# Vers_4_Moppy_Board.net
KiCad netlist of a schematic drawn in EAGLE
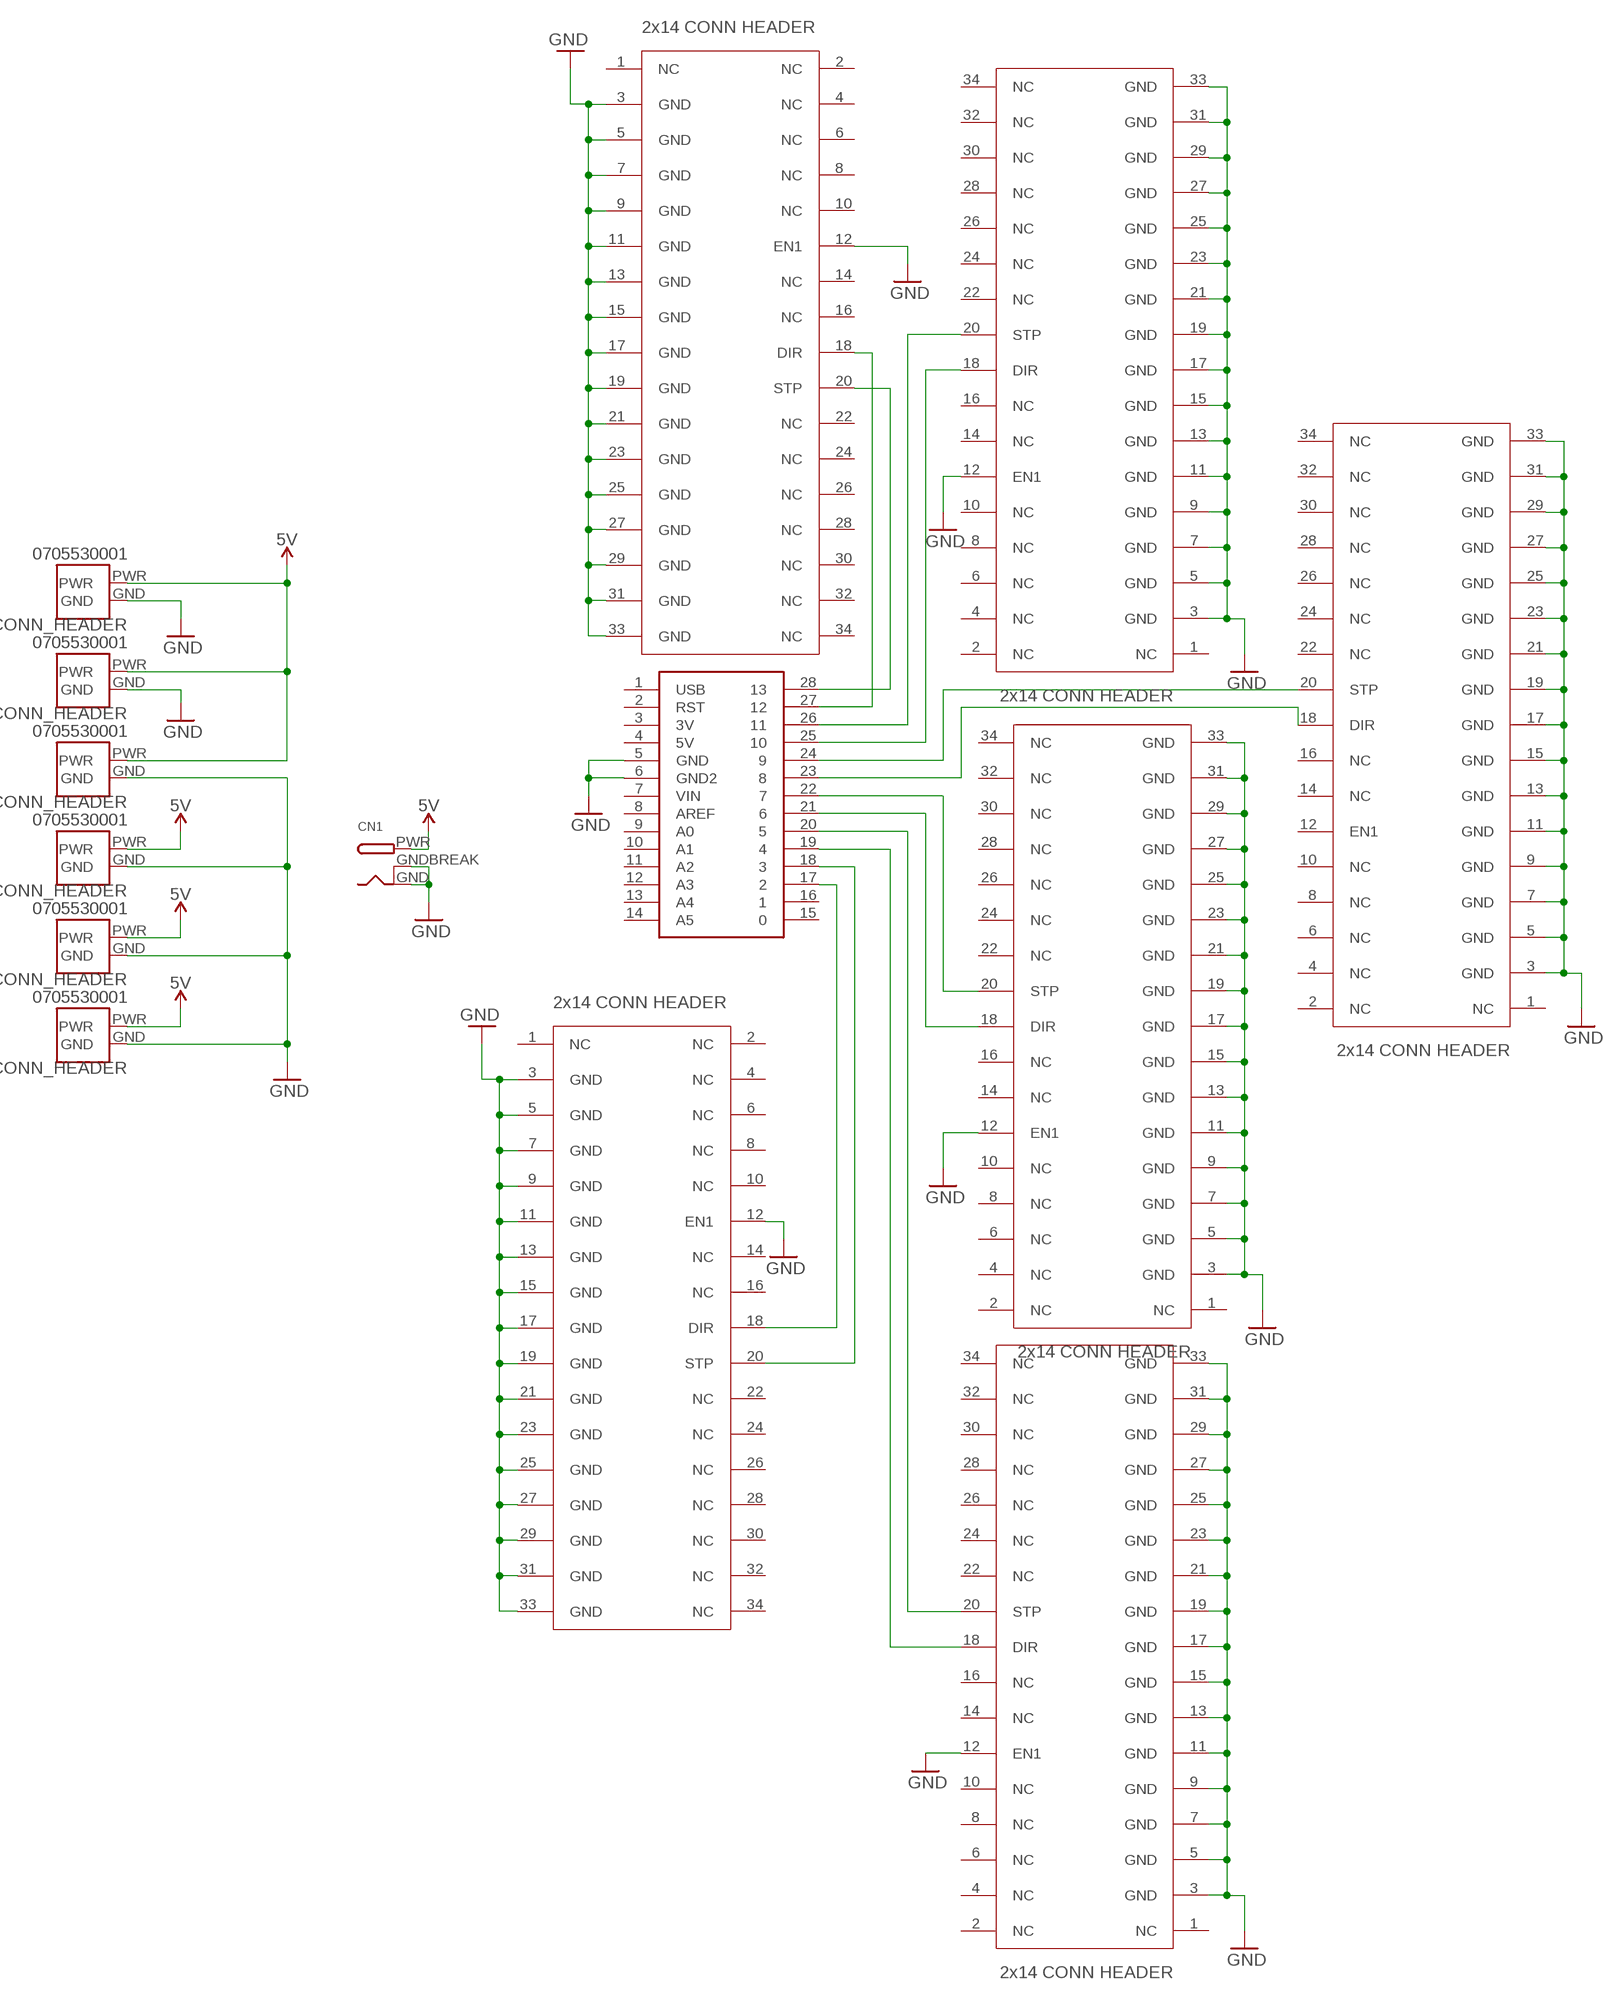
[diagram p0: schematic, sheet 1]

(export (version "E")
  (design (tool "Eeschema 10.0.6"))
  (components
    (comp (ref "CN1")
      (value "DCBARRELPTH")
      (footprint "eagle-import:DCJACK_2MM_PTH")
      (libsource (lib "eagle-import") (part "DCBARRELPTH"))
    )
    (comp (ref "U$1")
      (value "2X14_CONN_HEADER")
      (footprint "eagle-import:2X17_CONN_HEADER")
      (libsource (lib "eagle-import") (part "2X14_CONN_HEADER"))
    )
    (comp (ref "U$2")
      (value "2X14_CONN_HEADER")
      (footprint "eagle-import:2X17_CONN_HEADER")
      (libsource (lib "eagle-import") (part "2X14_CONN_HEADER"))
    )
    (comp (ref "U$3")
      (value "2X14_CONN_HEADER")
      (footprint "eagle-import:2X17_CONN_HEADER")
      (libsource (lib "eagle-import") (part "2X14_CONN_HEADER"))
    )
    (comp (ref "U$4")
      (value "2X14_CONN_HEADER")
      (footprint "eagle-import:2X17_CONN_HEADER")
      (libsource (lib "eagle-import") (part "2X14_CONN_HEADER"))
    )
    (comp (ref "U$5")
      (value "2X14_CONN_HEADER")
      (footprint "eagle-import:2X17_CONN_HEADER")
      (libsource (lib "eagle-import") (part "2X14_CONN_HEADER"))
    )
    (comp (ref "U$6")
      (value "2X14_CONN_HEADER")
      (footprint "eagle-import:2X17_CONN_HEADER")
      (libsource (lib "eagle-import") (part "2X14_CONN_HEADER"))
    )
    (comp (ref "U$8")
      (value "METROMINI")
      (footprint "eagle-import:METROMINI")
      (libsource (lib "eagle-import") (part "METROMINI"))
    )
    (comp (ref "X1")
      (value "0705530001")
      (footprint "eagle-import:MOLEX_0705530001")
      (fields (field (name "DIGI-KEY_PART_NUMBER") "WM4900-ND") (field (name "MF") "Molex"))
      (libsource (lib "eagle-import") (part "0705530001"))
    )
    (comp (ref "X2")
      (value "0705530001")
      (footprint "eagle-import:MOLEX_0705530001")
      (fields (field (name "DIGI-KEY_PART_NUMBER") "WM4900-ND") (field (name "MF") "Molex"))
      (libsource (lib "eagle-import") (part "0705530001"))
    )
    (comp (ref "X3")
      (value "0705530001")
      (footprint "eagle-import:MOLEX_0705530001")
      (fields (field (name "DIGI-KEY_PART_NUMBER") "WM4900-ND") (field (name "MF") "Molex"))
      (libsource (lib "eagle-import") (part "0705530001"))
    )
    (comp (ref "X4")
      (value "0705530001")
      (footprint "eagle-import:MOLEX_0705530001")
      (fields (field (name "DIGI-KEY_PART_NUMBER") "WM4900-ND") (field (name "MF") "Molex"))
      (libsource (lib "eagle-import") (part "0705530001"))
    )
    (comp (ref "X5")
      (value "0705530001")
      (footprint "eagle-import:MOLEX_0705530001")
      (fields (field (name "DIGI-KEY_PART_NUMBER") "WM4900-ND") (field (name "MF") "Molex"))
      (libsource (lib "eagle-import") (part "0705530001"))
    )
    (comp (ref "X6")
      (value "0705530001")
      (footprint "eagle-import:MOLEX_0705530001")
      (fields (field (name "DIGI-KEY_PART_NUMBER") "WM4900-ND") (field (name "MF") "Molex"))
      (libsource (lib "eagle-import") (part "0705530001"))
    )
  )
  (nets
    (net (code "1") (name "5V") (class "Default")
      (node (ref "CN1") (pin "PWR") (pinfunction "PWR_PWR") (pintype "power_in"))
      (node (ref "X1") (pin "PWR") (pinfunction "PWR_PWR") (pintype "passive"))
      (node (ref "X2") (pin "PWR") (pinfunction "PWR_PWR") (pintype "passive"))
      (node (ref "X3") (pin "PWR") (pinfunction "PWR_PWR") (pintype "passive"))
      (node (ref "X4") (pin "PWR") (pinfunction "PWR_PWR") (pintype "passive"))
      (node (ref "X5") (pin "PWR") (pinfunction "PWR_PWR") (pintype "passive"))
      (node (ref "X6") (pin "PWR") (pinfunction "PWR_PWR") (pintype "passive"))
    )
    (net (code "2") (name "GND") (class "Default")
      (node (ref "CN1") (pin "GND") (pinfunction "GND_GND") (pintype "power_in"))
      (node (ref "CN1") (pin "GNDBREAK") (pinfunction "GNDBREAK_GNDBREAK") (pintype "power_in"))
      (node (ref "U$1") (pin "11") (pinfunction "GND_11") (pintype "bidirectional"))
      (node (ref "U$1") (pin "12") (pinfunction "EN1_12") (pintype "bidirectional"))
      (node (ref "U$1") (pin "13") (pinfunction "GND_13") (pintype "bidirectional"))
      (node (ref "U$1") (pin "15") (pinfunction "GND_15") (pintype "bidirectional"))
      (node (ref "U$1") (pin "17") (pinfunction "GND_17") (pintype "bidirectional"))
      (node (ref "U$1") (pin "19") (pinfunction "GND_19") (pintype "bidirectional"))
      (node (ref "U$1") (pin "21") (pinfunction "GND_21") (pintype "bidirectional"))
      (node (ref "U$1") (pin "23") (pinfunction "GND_23") (pintype "bidirectional"))
      (node (ref "U$1") (pin "25") (pinfunction "GND_25") (pintype "bidirectional"))
      (node (ref "U$1") (pin "27") (pinfunction "GND_27") (pintype "bidirectional"))
      (node (ref "U$1") (pin "29") (pinfunction "GND_29") (pintype "bidirectional"))
      (node (ref "U$1") (pin "3") (pinfunction "GND_3") (pintype "bidirectional"))
      (node (ref "U$1") (pin "31") (pinfunction "GND_31") (pintype "bidirectional"))
      (node (ref "U$1") (pin "33") (pinfunction "GND_33") (pintype "bidirectional"))
      (node (ref "U$1") (pin "5") (pinfunction "GND_5") (pintype "bidirectional"))
      (node (ref "U$1") (pin "7") (pinfunction "GND_7") (pintype "bidirectional"))
      (node (ref "U$1") (pin "9") (pinfunction "GND_9") (pintype "bidirectional"))
      (node (ref "U$2") (pin "11") (pinfunction "GND_11") (pintype "bidirectional"))
      (node (ref "U$2") (pin "12") (pinfunction "EN1_12") (pintype "bidirectional"))
      (node (ref "U$2") (pin "13") (pinfunction "GND_13") (pintype "bidirectional"))
      (node (ref "U$2") (pin "15") (pinfunction "GND_15") (pintype "bidirectional"))
      (node (ref "U$2") (pin "17") (pinfunction "GND_17") (pintype "bidirectional"))
      (node (ref "U$2") (pin "19") (pinfunction "GND_19") (pintype "bidirectional"))
      (node (ref "U$2") (pin "21") (pinfunction "GND_21") (pintype "bidirectional"))
      (node (ref "U$2") (pin "23") (pinfunction "GND_23") (pintype "bidirectional"))
      (node (ref "U$2") (pin "25") (pinfunction "GND_25") (pintype "bidirectional"))
      (node (ref "U$2") (pin "27") (pinfunction "GND_27") (pintype "bidirectional"))
      (node (ref "U$2") (pin "29") (pinfunction "GND_29") (pintype "bidirectional"))
      (node (ref "U$2") (pin "3") (pinfunction "GND_3") (pintype "bidirectional"))
      (node (ref "U$2") (pin "31") (pinfunction "GND_31") (pintype "bidirectional"))
      (node (ref "U$2") (pin "33") (pinfunction "GND_33") (pintype "bidirectional"))
      (node (ref "U$2") (pin "5") (pinfunction "GND_5") (pintype "bidirectional"))
      (node (ref "U$2") (pin "7") (pinfunction "GND_7") (pintype "bidirectional"))
      (node (ref "U$2") (pin "9") (pinfunction "GND_9") (pintype "bidirectional"))
      (node (ref "U$3") (pin "11") (pinfunction "GND_11") (pintype "bidirectional"))
      (node (ref "U$3") (pin "12") (pinfunction "EN1_12") (pintype "bidirectional"))
      (node (ref "U$3") (pin "13") (pinfunction "GND_13") (pintype "bidirectional"))
      (node (ref "U$3") (pin "15") (pinfunction "GND_15") (pintype "bidirectional"))
      (node (ref "U$3") (pin "17") (pinfunction "GND_17") (pintype "bidirectional"))
      (node (ref "U$3") (pin "19") (pinfunction "GND_19") (pintype "bidirectional"))
      (node (ref "U$3") (pin "21") (pinfunction "GND_21") (pintype "bidirectional"))
      (node (ref "U$3") (pin "23") (pinfunction "GND_23") (pintype "bidirectional"))
      (node (ref "U$3") (pin "25") (pinfunction "GND_25") (pintype "bidirectional"))
      (node (ref "U$3") (pin "27") (pinfunction "GND_27") (pintype "bidirectional"))
      (node (ref "U$3") (pin "29") (pinfunction "GND_29") (pintype "bidirectional"))
      (node (ref "U$3") (pin "3") (pinfunction "GND_3") (pintype "bidirectional"))
      (node (ref "U$3") (pin "31") (pinfunction "GND_31") (pintype "bidirectional"))
      (node (ref "U$3") (pin "33") (pinfunction "GND_33") (pintype "bidirectional"))
      (node (ref "U$3") (pin "5") (pinfunction "GND_5") (pintype "bidirectional"))
      (node (ref "U$3") (pin "7") (pinfunction "GND_7") (pintype "bidirectional"))
      (node (ref "U$3") (pin "9") (pinfunction "GND_9") (pintype "bidirectional"))
      (node (ref "U$4") (pin "11") (pinfunction "GND_11") (pintype "bidirectional"))
      (node (ref "U$4") (pin "12") (pinfunction "EN1_12") (pintype "bidirectional"))
      (node (ref "U$4") (pin "13") (pinfunction "GND_13") (pintype "bidirectional"))
      (node (ref "U$4") (pin "15") (pinfunction "GND_15") (pintype "bidirectional"))
      (node (ref "U$4") (pin "17") (pinfunction "GND_17") (pintype "bidirectional"))
      (node (ref "U$4") (pin "19") (pinfunction "GND_19") (pintype "bidirectional"))
      (node (ref "U$4") (pin "21") (pinfunction "GND_21") (pintype "bidirectional"))
      (node (ref "U$4") (pin "23") (pinfunction "GND_23") (pintype "bidirectional"))
      (node (ref "U$4") (pin "25") (pinfunction "GND_25") (pintype "bidirectional"))
      (node (ref "U$4") (pin "27") (pinfunction "GND_27") (pintype "bidirectional"))
      (node (ref "U$4") (pin "29") (pinfunction "GND_29") (pintype "bidirectional"))
      (node (ref "U$4") (pin "3") (pinfunction "GND_3") (pintype "bidirectional"))
      (node (ref "U$4") (pin "31") (pinfunction "GND_31") (pintype "bidirectional"))
      (node (ref "U$4") (pin "33") (pinfunction "GND_33") (pintype "bidirectional"))
      (node (ref "U$4") (pin "5") (pinfunction "GND_5") (pintype "bidirectional"))
      (node (ref "U$4") (pin "7") (pinfunction "GND_7") (pintype "bidirectional"))
      (node (ref "U$4") (pin "9") (pinfunction "GND_9") (pintype "bidirectional"))
      (node (ref "U$5") (pin "11") (pinfunction "GND_11") (pintype "bidirectional"))
      (node (ref "U$5") (pin "12") (pinfunction "EN1_12") (pintype "bidirectional"))
      (node (ref "U$5") (pin "13") (pinfunction "GND_13") (pintype "bidirectional"))
      (node (ref "U$5") (pin "15") (pinfunction "GND_15") (pintype "bidirectional"))
      (node (ref "U$5") (pin "17") (pinfunction "GND_17") (pintype "bidirectional"))
      (node (ref "U$5") (pin "19") (pinfunction "GND_19") (pintype "bidirectional"))
      (node (ref "U$5") (pin "21") (pinfunction "GND_21") (pintype "bidirectional"))
      (node (ref "U$5") (pin "23") (pinfunction "GND_23") (pintype "bidirectional"))
      (node (ref "U$5") (pin "25") (pinfunction "GND_25") (pintype "bidirectional"))
      (node (ref "U$5") (pin "27") (pinfunction "GND_27") (pintype "bidirectional"))
      (node (ref "U$5") (pin "29") (pinfunction "GND_29") (pintype "bidirectional"))
      (node (ref "U$5") (pin "3") (pinfunction "GND_3") (pintype "bidirectional"))
      (node (ref "U$5") (pin "31") (pinfunction "GND_31") (pintype "bidirectional"))
      (node (ref "U$5") (pin "33") (pinfunction "GND_33") (pintype "bidirectional"))
      (node (ref "U$5") (pin "5") (pinfunction "GND_5") (pintype "bidirectional"))
      (node (ref "U$5") (pin "7") (pinfunction "GND_7") (pintype "bidirectional"))
      (node (ref "U$5") (pin "9") (pinfunction "GND_9") (pintype "bidirectional"))
      (node (ref "U$6") (pin "11") (pinfunction "GND_11") (pintype "bidirectional"))
      (node (ref "U$6") (pin "13") (pinfunction "GND_13") (pintype "bidirectional"))
      (node (ref "U$6") (pin "15") (pinfunction "GND_15") (pintype "bidirectional"))
      (node (ref "U$6") (pin "17") (pinfunction "GND_17") (pintype "bidirectional"))
      (node (ref "U$6") (pin "19") (pinfunction "GND_19") (pintype "bidirectional"))
      (node (ref "U$6") (pin "21") (pinfunction "GND_21") (pintype "bidirectional"))
      (node (ref "U$6") (pin "23") (pinfunction "GND_23") (pintype "bidirectional"))
      (node (ref "U$6") (pin "25") (pinfunction "GND_25") (pintype "bidirectional"))
      (node (ref "U$6") (pin "27") (pinfunction "GND_27") (pintype "bidirectional"))
      (node (ref "U$6") (pin "29") (pinfunction "GND_29") (pintype "bidirectional"))
      (node (ref "U$6") (pin "3") (pinfunction "GND_3") (pintype "bidirectional"))
      (node (ref "U$6") (pin "31") (pinfunction "GND_31") (pintype "bidirectional"))
      (node (ref "U$6") (pin "33") (pinfunction "GND_33") (pintype "bidirectional"))
      (node (ref "U$6") (pin "5") (pinfunction "GND_5") (pintype "bidirectional"))
      (node (ref "U$6") (pin "7") (pinfunction "GND_7") (pintype "bidirectional"))
      (node (ref "U$6") (pin "9") (pinfunction "GND_9") (pintype "bidirectional"))
      (node (ref "U$8") (pin "5") (pinfunction "GND_5") (pintype "bidirectional"))
      (node (ref "U$8") (pin "6") (pinfunction "GND2_6") (pintype "bidirectional"))
      (node (ref "X1") (pin "GND") (pinfunction "GND_GND") (pintype "passive"))
      (node (ref "X2") (pin "GND") (pinfunction "GND_GND") (pintype "passive"))
      (node (ref "X3") (pin "GND") (pinfunction "GND_GND") (pintype "passive"))
      (node (ref "X4") (pin "GND") (pinfunction "GND_GND") (pintype "passive"))
      (node (ref "X5") (pin "GND") (pinfunction "GND_GND") (pintype "passive"))
      (node (ref "X6") (pin "GND") (pinfunction "GND_GND") (pintype "passive"))
    )
    (net (code "3") (name "Net-(U$1-DIR)") (class "Default")
      (node (ref "U$1") (pin "18") (pinfunction "DIR_18") (pintype "bidirectional"))
      (node (ref "U$8") (pin "17") (pinfunction "2_17") (pintype "bidirectional"))
    )
    (net (code "4") (name "Net-(U$1-STP)") (class "Default")
      (node (ref "U$1") (pin "20") (pinfunction "STP_20") (pintype "bidirectional"))
      (node (ref "U$8") (pin "18") (pinfunction "3_18") (pintype "bidirectional"))
    )
    (net (code "5") (name "Net-(U$2-DIR)") (class "Default")
      (node (ref "U$2") (pin "18") (pinfunction "DIR_18") (pintype "bidirectional"))
      (node (ref "U$8") (pin "27") (pinfunction "12_27") (pintype "bidirectional"))
    )
    (net (code "6") (name "Net-(U$2-STP)") (class "Default")
      (node (ref "U$2") (pin "20") (pinfunction "STP_20") (pintype "bidirectional"))
      (node (ref "U$8") (pin "28") (pinfunction "13_28") (pintype "bidirectional"))
    )
    (net (code "7") (name "Net-(U$3-DIR)") (class "Default")
      (node (ref "U$3") (pin "18") (pinfunction "DIR_18") (pintype "bidirectional"))
      (node (ref "U$8") (pin "25") (pinfunction "10_25") (pintype "bidirectional"))
    )
    (net (code "8") (name "Net-(U$3-STP)") (class "Default")
      (node (ref "U$3") (pin "20") (pinfunction "STP_20") (pintype "bidirectional"))
      (node (ref "U$8") (pin "26") (pinfunction "11_26") (pintype "bidirectional"))
    )
    (net (code "9") (name "Net-(U$4-DIR)") (class "Default")
      (node (ref "U$4") (pin "18") (pinfunction "DIR_18") (pintype "bidirectional"))
      (node (ref "U$8") (pin "19") (pinfunction "4_19") (pintype "bidirectional"))
    )
    (net (code "10") (name "Net-(U$4-STP)") (class "Default")
      (node (ref "U$4") (pin "20") (pinfunction "STP_20") (pintype "bidirectional"))
      (node (ref "U$8") (pin "20") (pinfunction "5_20") (pintype "bidirectional"))
    )
    (net (code "11") (name "Net-(U$5-DIR)") (class "Default")
      (node (ref "U$5") (pin "18") (pinfunction "DIR_18") (pintype "bidirectional"))
      (node (ref "U$8") (pin "21") (pinfunction "6_21") (pintype "bidirectional"))
    )
    (net (code "12") (name "Net-(U$5-STP)") (class "Default")
      (node (ref "U$5") (pin "20") (pinfunction "STP_20") (pintype "bidirectional"))
      (node (ref "U$8") (pin "22") (pinfunction "7_22") (pintype "bidirectional"))
    )
    (net (code "13") (name "Net-(U$6-DIR)") (class "Default")
      (node (ref "U$6") (pin "18") (pinfunction "DIR_18") (pintype "bidirectional"))
      (node (ref "U$8") (pin "23") (pinfunction "8_23") (pintype "bidirectional"))
    )
    (net (code "14") (name "Net-(U$6-STP)") (class "Default")
      (node (ref "U$6") (pin "20") (pinfunction "STP_20") (pintype "bidirectional"))
      (node (ref "U$8") (pin "24") (pinfunction "9_24") (pintype "bidirectional"))
    )
    (net (code "15") (name "unconnected-(U$1-NC-Pad1)") (class "Default")
      (node (ref "U$1") (pin "1") (pinfunction "NC_1") (pintype "bidirectional"))
    )
    (net (code "16") (name "unconnected-(U$1-NC-Pad2)") (class "Default")
      (node (ref "U$1") (pin "2") (pinfunction "NC_2") (pintype "bidirectional"))
    )
    (net (code "17") (name "unconnected-(U$1-NC-Pad4)") (class "Default")
      (node (ref "U$1") (pin "4") (pinfunction "NC_4") (pintype "bidirectional"))
    )
    (net (code "18") (name "unconnected-(U$1-NC-Pad6)") (class "Default")
      (node (ref "U$1") (pin "6") (pinfunction "NC_6") (pintype "bidirectional"))
    )
    (net (code "19") (name "unconnected-(U$1-NC-Pad8)") (class "Default")
      (node (ref "U$1") (pin "8") (pinfunction "NC_8") (pintype "bidirectional"))
    )
    (net (code "20") (name "unconnected-(U$1-NC-Pad10)") (class "Default")
      (node (ref "U$1") (pin "10") (pinfunction "NC_10") (pintype "bidirectional"))
    )
    (net (code "21") (name "unconnected-(U$1-NC-Pad14)") (class "Default")
      (node (ref "U$1") (pin "14") (pinfunction "NC_14") (pintype "bidirectional"))
    )
    (net (code "22") (name "unconnected-(U$1-NC-Pad16)") (class "Default")
      (node (ref "U$1") (pin "16") (pinfunction "NC_16") (pintype "bidirectional"))
    )
    (net (code "23") (name "unconnected-(U$1-NC-Pad22)") (class "Default")
      (node (ref "U$1") (pin "22") (pinfunction "NC_22") (pintype "bidirectional"))
    )
    (net (code "24") (name "unconnected-(U$1-NC-Pad24)") (class "Default")
      (node (ref "U$1") (pin "24") (pinfunction "NC_24") (pintype "bidirectional"))
    )
    (net (code "25") (name "unconnected-(U$1-NC-Pad26)") (class "Default")
      (node (ref "U$1") (pin "26") (pinfunction "NC_26") (pintype "bidirectional"))
    )
    (net (code "26") (name "unconnected-(U$1-NC-Pad28)") (class "Default")
      (node (ref "U$1") (pin "28") (pinfunction "NC_28") (pintype "bidirectional"))
    )
    (net (code "27") (name "unconnected-(U$1-NC-Pad30)") (class "Default")
      (node (ref "U$1") (pin "30") (pinfunction "NC_30") (pintype "bidirectional"))
    )
    (net (code "28") (name "unconnected-(U$1-NC-Pad32)") (class "Default")
      (node (ref "U$1") (pin "32") (pinfunction "NC_32") (pintype "bidirectional"))
    )
    (net (code "29") (name "unconnected-(U$1-NC-Pad34)") (class "Default")
      (node (ref "U$1") (pin "34") (pinfunction "NC_34") (pintype "bidirectional"))
    )
    (net (code "30") (name "unconnected-(U$2-NC-Pad1)") (class "Default")
      (node (ref "U$2") (pin "1") (pinfunction "NC_1") (pintype "bidirectional"))
    )
    (net (code "31") (name "unconnected-(U$2-NC-Pad2)") (class "Default")
      (node (ref "U$2") (pin "2") (pinfunction "NC_2") (pintype "bidirectional"))
    )
    (net (code "32") (name "unconnected-(U$2-NC-Pad4)") (class "Default")
      (node (ref "U$2") (pin "4") (pinfunction "NC_4") (pintype "bidirectional"))
    )
    (net (code "33") (name "unconnected-(U$2-NC-Pad6)") (class "Default")
      (node (ref "U$2") (pin "6") (pinfunction "NC_6") (pintype "bidirectional"))
    )
    (net (code "34") (name "unconnected-(U$2-NC-Pad8)") (class "Default")
      (node (ref "U$2") (pin "8") (pinfunction "NC_8") (pintype "bidirectional"))
    )
    (net (code "35") (name "unconnected-(U$2-NC-Pad10)") (class "Default")
      (node (ref "U$2") (pin "10") (pinfunction "NC_10") (pintype "bidirectional"))
    )
    (net (code "36") (name "unconnected-(U$2-NC-Pad14)") (class "Default")
      (node (ref "U$2") (pin "14") (pinfunction "NC_14") (pintype "bidirectional"))
    )
    (net (code "37") (name "unconnected-(U$2-NC-Pad16)") (class "Default")
      (node (ref "U$2") (pin "16") (pinfunction "NC_16") (pintype "bidirectional"))
    )
    (net (code "38") (name "unconnected-(U$2-NC-Pad22)") (class "Default")
      (node (ref "U$2") (pin "22") (pinfunction "NC_22") (pintype "bidirectional"))
    )
    (net (code "39") (name "unconnected-(U$2-NC-Pad24)") (class "Default")
      (node (ref "U$2") (pin "24") (pinfunction "NC_24") (pintype "bidirectional"))
    )
    (net (code "40") (name "unconnected-(U$2-NC-Pad26)") (class "Default")
      (node (ref "U$2") (pin "26") (pinfunction "NC_26") (pintype "bidirectional"))
    )
    (net (code "41") (name "unconnected-(U$2-NC-Pad28)") (class "Default")
      (node (ref "U$2") (pin "28") (pinfunction "NC_28") (pintype "bidirectional"))
    )
    (net (code "42") (name "unconnected-(U$2-NC-Pad30)") (class "Default")
      (node (ref "U$2") (pin "30") (pinfunction "NC_30") (pintype "bidirectional"))
    )
    (net (code "43") (name "unconnected-(U$2-NC-Pad32)") (class "Default")
      (node (ref "U$2") (pin "32") (pinfunction "NC_32") (pintype "bidirectional"))
    )
    (net (code "44") (name "unconnected-(U$2-NC-Pad34)") (class "Default")
      (node (ref "U$2") (pin "34") (pinfunction "NC_34") (pintype "bidirectional"))
    )
    (net (code "45") (name "unconnected-(U$3-NC-Pad1)") (class "Default")
      (node (ref "U$3") (pin "1") (pinfunction "NC_1") (pintype "bidirectional"))
    )
    (net (code "46") (name "unconnected-(U$3-NC-Pad2)") (class "Default")
      (node (ref "U$3") (pin "2") (pinfunction "NC_2") (pintype "bidirectional"))
    )
    (net (code "47") (name "unconnected-(U$3-NC-Pad4)") (class "Default")
      (node (ref "U$3") (pin "4") (pinfunction "NC_4") (pintype "bidirectional"))
    )
    (net (code "48") (name "unconnected-(U$3-NC-Pad6)") (class "Default")
      (node (ref "U$3") (pin "6") (pinfunction "NC_6") (pintype "bidirectional"))
    )
    (net (code "49") (name "unconnected-(U$3-NC-Pad8)") (class "Default")
      (node (ref "U$3") (pin "8") (pinfunction "NC_8") (pintype "bidirectional"))
    )
    (net (code "50") (name "unconnected-(U$3-NC-Pad10)") (class "Default")
      (node (ref "U$3") (pin "10") (pinfunction "NC_10") (pintype "bidirectional"))
    )
    (net (code "51") (name "unconnected-(U$3-NC-Pad14)") (class "Default")
      (node (ref "U$3") (pin "14") (pinfunction "NC_14") (pintype "bidirectional"))
    )
    (net (code "52") (name "unconnected-(U$3-NC-Pad16)") (class "Default")
      (node (ref "U$3") (pin "16") (pinfunction "NC_16") (pintype "bidirectional"))
    )
    (net (code "53") (name "unconnected-(U$3-NC-Pad22)") (class "Default")
      (node (ref "U$3") (pin "22") (pinfunction "NC_22") (pintype "bidirectional"))
    )
    (net (code "54") (name "unconnected-(U$3-NC-Pad24)") (class "Default")
      (node (ref "U$3") (pin "24") (pinfunction "NC_24") (pintype "bidirectional"))
    )
    (net (code "55") (name "unconnected-(U$3-NC-Pad26)") (class "Default")
      (node (ref "U$3") (pin "26") (pinfunction "NC_26") (pintype "bidirectional"))
    )
    (net (code "56") (name "unconnected-(U$3-NC-Pad28)") (class "Default")
      (node (ref "U$3") (pin "28") (pinfunction "NC_28") (pintype "bidirectional"))
    )
    (net (code "57") (name "unconnected-(U$3-NC-Pad30)") (class "Default")
      (node (ref "U$3") (pin "30") (pinfunction "NC_30") (pintype "bidirectional"))
    )
    (net (code "58") (name "unconnected-(U$3-NC-Pad32)") (class "Default")
      (node (ref "U$3") (pin "32") (pinfunction "NC_32") (pintype "bidirectional"))
    )
    (net (code "59") (name "unconnected-(U$3-NC-Pad34)") (class "Default")
      (node (ref "U$3") (pin "34") (pinfunction "NC_34") (pintype "bidirectional"))
    )
    (net (code "60") (name "unconnected-(U$4-NC-Pad1)") (class "Default")
      (node (ref "U$4") (pin "1") (pinfunction "NC_1") (pintype "bidirectional"))
    )
    (net (code "61") (name "unconnected-(U$4-NC-Pad2)") (class "Default")
      (node (ref "U$4") (pin "2") (pinfunction "NC_2") (pintype "bidirectional"))
    )
    (net (code "62") (name "unconnected-(U$4-NC-Pad4)") (class "Default")
      (node (ref "U$4") (pin "4") (pinfunction "NC_4") (pintype "bidirectional"))
    )
    (net (code "63") (name "unconnected-(U$4-NC-Pad6)") (class "Default")
      (node (ref "U$4") (pin "6") (pinfunction "NC_6") (pintype "bidirectional"))
    )
    (net (code "64") (name "unconnected-(U$4-NC-Pad8)") (class "Default")
      (node (ref "U$4") (pin "8") (pinfunction "NC_8") (pintype "bidirectional"))
    )
    (net (code "65") (name "unconnected-(U$4-NC-Pad10)") (class "Default")
      (node (ref "U$4") (pin "10") (pinfunction "NC_10") (pintype "bidirectional"))
    )
    (net (code "66") (name "unconnected-(U$4-NC-Pad14)") (class "Default")
      (node (ref "U$4") (pin "14") (pinfunction "NC_14") (pintype "bidirectional"))
    )
    (net (code "67") (name "unconnected-(U$4-NC-Pad16)") (class "Default")
      (node (ref "U$4") (pin "16") (pinfunction "NC_16") (pintype "bidirectional"))
    )
    (net (code "68") (name "unconnected-(U$4-NC-Pad22)") (class "Default")
      (node (ref "U$4") (pin "22") (pinfunction "NC_22") (pintype "bidirectional"))
    )
    (net (code "69") (name "unconnected-(U$4-NC-Pad24)") (class "Default")
      (node (ref "U$4") (pin "24") (pinfunction "NC_24") (pintype "bidirectional"))
    )
    (net (code "70") (name "unconnected-(U$4-NC-Pad26)") (class "Default")
      (node (ref "U$4") (pin "26") (pinfunction "NC_26") (pintype "bidirectional"))
    )
    (net (code "71") (name "unconnected-(U$4-NC-Pad28)") (class "Default")
      (node (ref "U$4") (pin "28") (pinfunction "NC_28") (pintype "bidirectional"))
    )
    (net (code "72") (name "unconnected-(U$4-NC-Pad30)") (class "Default")
      (node (ref "U$4") (pin "30") (pinfunction "NC_30") (pintype "bidirectional"))
    )
    (net (code "73") (name "unconnected-(U$4-NC-Pad32)") (class "Default")
      (node (ref "U$4") (pin "32") (pinfunction "NC_32") (pintype "bidirectional"))
    )
    (net (code "74") (name "unconnected-(U$4-NC-Pad34)") (class "Default")
      (node (ref "U$4") (pin "34") (pinfunction "NC_34") (pintype "bidirectional"))
    )
    (net (code "75") (name "unconnected-(U$5-NC-Pad1)") (class "Default")
      (node (ref "U$5") (pin "1") (pinfunction "NC_1") (pintype "bidirectional"))
    )
    (net (code "76") (name "unconnected-(U$5-NC-Pad2)") (class "Default")
      (node (ref "U$5") (pin "2") (pinfunction "NC_2") (pintype "bidirectional"))
    )
    (net (code "77") (name "unconnected-(U$5-NC-Pad4)") (class "Default")
      (node (ref "U$5") (pin "4") (pinfunction "NC_4") (pintype "bidirectional"))
    )
    (net (code "78") (name "unconnected-(U$5-NC-Pad6)") (class "Default")
      (node (ref "U$5") (pin "6") (pinfunction "NC_6") (pintype "bidirectional"))
    )
    (net (code "79") (name "unconnected-(U$5-NC-Pad8)") (class "Default")
      (node (ref "U$5") (pin "8") (pinfunction "NC_8") (pintype "bidirectional"))
    )
    (net (code "80") (name "unconnected-(U$5-NC-Pad10)") (class "Default")
      (node (ref "U$5") (pin "10") (pinfunction "NC_10") (pintype "bidirectional"))
    )
    (net (code "81") (name "unconnected-(U$5-NC-Pad14)") (class "Default")
      (node (ref "U$5") (pin "14") (pinfunction "NC_14") (pintype "bidirectional"))
    )
    (net (code "82") (name "unconnected-(U$5-NC-Pad16)") (class "Default")
      (node (ref "U$5") (pin "16") (pinfunction "NC_16") (pintype "bidirectional"))
    )
    (net (code "83") (name "unconnected-(U$5-NC-Pad22)") (class "Default")
      (node (ref "U$5") (pin "22") (pinfunction "NC_22") (pintype "bidirectional"))
    )
    (net (code "84") (name "unconnected-(U$5-NC-Pad24)") (class "Default")
      (node (ref "U$5") (pin "24") (pinfunction "NC_24") (pintype "bidirectional"))
    )
    (net (code "85") (name "unconnected-(U$5-NC-Pad26)") (class "Default")
      (node (ref "U$5") (pin "26") (pinfunction "NC_26") (pintype "bidirectional"))
    )
    (net (code "86") (name "unconnected-(U$5-NC-Pad28)") (class "Default")
      (node (ref "U$5") (pin "28") (pinfunction "NC_28") (pintype "bidirectional"))
    )
    (net (code "87") (name "unconnected-(U$5-NC-Pad30)") (class "Default")
      (node (ref "U$5") (pin "30") (pinfunction "NC_30") (pintype "bidirectional"))
    )
    (net (code "88") (name "unconnected-(U$5-NC-Pad32)") (class "Default")
      (node (ref "U$5") (pin "32") (pinfunction "NC_32") (pintype "bidirectional"))
    )
    (net (code "89") (name "unconnected-(U$5-NC-Pad34)") (class "Default")
      (node (ref "U$5") (pin "34") (pinfunction "NC_34") (pintype "bidirectional"))
    )
    (net (code "90") (name "unconnected-(U$6-EN1-Pad12)") (class "Default")
      (node (ref "U$6") (pin "12") (pinfunction "EN1_12") (pintype "bidirectional"))
    )
    (net (code "91") (name "unconnected-(U$6-NC-Pad1)") (class "Default")
      (node (ref "U$6") (pin "1") (pinfunction "NC_1") (pintype "bidirectional"))
    )
    (net (code "92") (name "unconnected-(U$6-NC-Pad2)") (class "Default")
      (node (ref "U$6") (pin "2") (pinfunction "NC_2") (pintype "bidirectional"))
    )
    (net (code "93") (name "unconnected-(U$6-NC-Pad4)") (class "Default")
      (node (ref "U$6") (pin "4") (pinfunction "NC_4") (pintype "bidirectional"))
    )
    (net (code "94") (name "unconnected-(U$6-NC-Pad6)") (class "Default")
      (node (ref "U$6") (pin "6") (pinfunction "NC_6") (pintype "bidirectional"))
    )
    (net (code "95") (name "unconnected-(U$6-NC-Pad8)") (class "Default")
      (node (ref "U$6") (pin "8") (pinfunction "NC_8") (pintype "bidirectional"))
    )
    (net (code "96") (name "unconnected-(U$6-NC-Pad10)") (class "Default")
      (node (ref "U$6") (pin "10") (pinfunction "NC_10") (pintype "bidirectional"))
    )
    (net (code "97") (name "unconnected-(U$6-NC-Pad14)") (class "Default")
      (node (ref "U$6") (pin "14") (pinfunction "NC_14") (pintype "bidirectional"))
    )
    (net (code "98") (name "unconnected-(U$6-NC-Pad16)") (class "Default")
      (node (ref "U$6") (pin "16") (pinfunction "NC_16") (pintype "bidirectional"))
    )
    (net (code "99") (name "unconnected-(U$6-NC-Pad22)") (class "Default")
      (node (ref "U$6") (pin "22") (pinfunction "NC_22") (pintype "bidirectional"))
    )
    (net (code "100") (name "unconnected-(U$6-NC-Pad24)") (class "Default")
      (node (ref "U$6") (pin "24") (pinfunction "NC_24") (pintype "bidirectional"))
    )
    (net (code "101") (name "unconnected-(U$6-NC-Pad26)") (class "Default")
      (node (ref "U$6") (pin "26") (pinfunction "NC_26") (pintype "bidirectional"))
    )
    (net (code "102") (name "unconnected-(U$6-NC-Pad28)") (class "Default")
      (node (ref "U$6") (pin "28") (pinfunction "NC_28") (pintype "bidirectional"))
    )
    (net (code "103") (name "unconnected-(U$6-NC-Pad30)") (class "Default")
      (node (ref "U$6") (pin "30") (pinfunction "NC_30") (pintype "bidirectional"))
    )
    (net (code "104") (name "unconnected-(U$6-NC-Pad32)") (class "Default")
      (node (ref "U$6") (pin "32") (pinfunction "NC_32") (pintype "bidirectional"))
    )
    (net (code "105") (name "unconnected-(U$6-NC-Pad34)") (class "Default")
      (node (ref "U$6") (pin "34") (pinfunction "NC_34") (pintype "bidirectional"))
    )
    (net (code "106") (name "unconnected-(U$8-0-Pad15)") (class "Default")
      (node (ref "U$8") (pin "15") (pinfunction "0_15") (pintype "bidirectional"))
    )
    (net (code "107") (name "unconnected-(U$8-1-Pad16)") (class "Default")
      (node (ref "U$8") (pin "16") (pinfunction "1_16") (pintype "bidirectional"))
    )
    (net (code "108") (name "unconnected-(U$8-3V-Pad3)") (class "Default")
      (node (ref "U$8") (pin "3") (pinfunction "3V_3") (pintype "bidirectional"))
    )
    (net (code "109") (name "unconnected-(U$8-5V-Pad4)") (class "Default")
      (node (ref "U$8") (pin "4") (pinfunction "5V_4") (pintype "bidirectional"))
    )
    (net (code "110") (name "unconnected-(U$8-A0-Pad9)") (class "Default")
      (node (ref "U$8") (pin "9") (pinfunction "A0_9") (pintype "bidirectional"))
    )
    (net (code "111") (name "unconnected-(U$8-A1-Pad10)") (class "Default")
      (node (ref "U$8") (pin "10") (pinfunction "A1_10") (pintype "bidirectional"))
    )
    (net (code "112") (name "unconnected-(U$8-A2-Pad11)") (class "Default")
      (node (ref "U$8") (pin "11") (pinfunction "A2_11") (pintype "bidirectional"))
    )
    (net (code "113") (name "unconnected-(U$8-A3-Pad12)") (class "Default")
      (node (ref "U$8") (pin "12") (pinfunction "A3_12") (pintype "bidirectional"))
    )
    (net (code "114") (name "unconnected-(U$8-A4-Pad13)") (class "Default")
      (node (ref "U$8") (pin "13") (pinfunction "A4_13") (pintype "bidirectional"))
    )
    (net (code "115") (name "unconnected-(U$8-A5-Pad14)") (class "Default")
      (node (ref "U$8") (pin "14") (pinfunction "A5_14") (pintype "bidirectional"))
    )
    (net (code "116") (name "unconnected-(U$8-AREF-Pad8)") (class "Default")
      (node (ref "U$8") (pin "8") (pinfunction "AREF_8") (pintype "bidirectional"))
    )
    (net (code "117") (name "unconnected-(U$8-RST-Pad2)") (class "Default")
      (node (ref "U$8") (pin "2") (pinfunction "RST_2") (pintype "bidirectional"))
    )
    (net (code "118") (name "unconnected-(U$8-USB-Pad1)") (class "Default")
      (node (ref "U$8") (pin "1") (pinfunction "USB_1") (pintype "bidirectional"))
    )
    (net (code "119") (name "unconnected-(U$8-VIN-Pad7)") (class "Default")
      (node (ref "U$8") (pin "7") (pinfunction "VIN_7") (pintype "bidirectional"))
    )
  )
)
